# TEMP.net
KiCad netlist of a schematic drawn in EAGLE
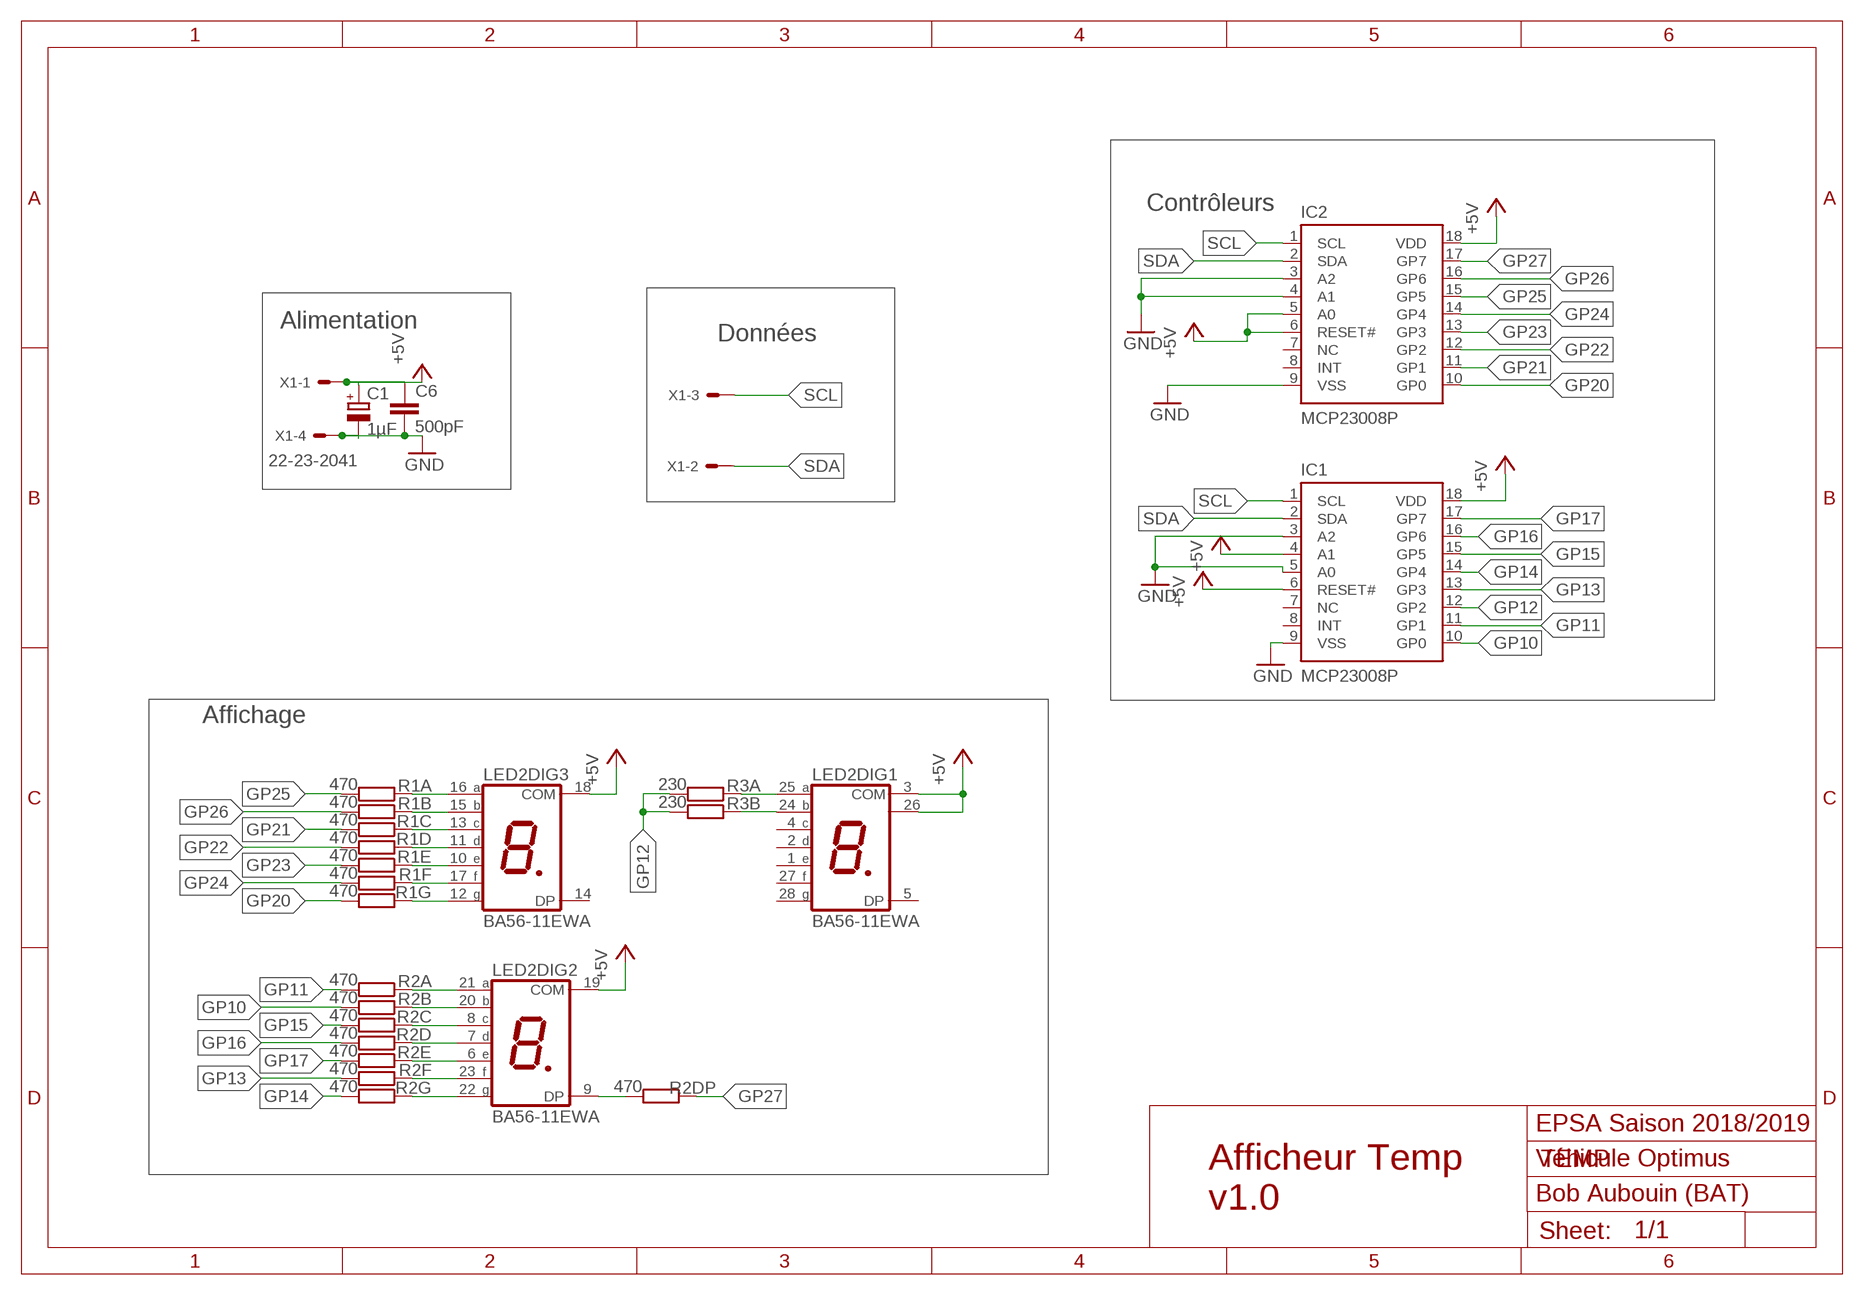
[diagram p0: schematic, sheet 1]

(export (version "E")
  (design (tool "Eeschema 10.0.6"))
  (components
    (comp (ref "C1")
      (value "1µF")
      (footprint "eagle-import:B45181A")
      (libsource (lib "eagle-import") (part "CPOL-EUB45181A"))
    )
    (comp (ref "C6")
      (value "500pF")
      (footprint "eagle-import:C025-025X050")
      (libsource (lib "eagle-import") (part "C-EU025-025X050"))
    )
    (comp (ref "IC1")
      (value "MCP23008P")
      (footprint "eagle-import:DIL18")
      (libsource (lib "eagle-import") (part "MCP23008P"))
    )
    (comp (ref "IC2")
      (value "MCP23008P")
      (footprint "eagle-import:DIL18")
      (libsource (lib "eagle-import") (part "MCP23008P"))
    )
    (comp (ref "LED2")
      (value "BA56-11EWA")
      (footprint "eagle-import:BA_BC56")
      (libsource (lib "eagle-import") (part "B?56-11WAAE"))
    )
    (comp (ref "R1A")
      (value "470")
      (footprint "eagle-import:0204_7")
      (libsource (lib "eagle-import") (part "R-EU_0204/7"))
    )
    (comp (ref "R1B")
      (value "470")
      (footprint "eagle-import:0204_7")
      (libsource (lib "eagle-import") (part "R-EU_0204/7"))
    )
    (comp (ref "R1C")
      (value "470")
      (footprint "eagle-import:0204_7")
      (libsource (lib "eagle-import") (part "R-EU_0204/7"))
    )
    (comp (ref "R1D")
      (value "470")
      (footprint "eagle-import:0204_7")
      (libsource (lib "eagle-import") (part "R-EU_0204/7"))
    )
    (comp (ref "R1E")
      (value "470")
      (footprint "eagle-import:0204_7")
      (libsource (lib "eagle-import") (part "R-EU_0204/7"))
    )
    (comp (ref "R1F")
      (value "470")
      (footprint "eagle-import:0204_7")
      (libsource (lib "eagle-import") (part "R-EU_0204/7"))
    )
    (comp (ref "R1G")
      (value "470")
      (footprint "eagle-import:0204_7")
      (libsource (lib "eagle-import") (part "R-EU_0204/7"))
    )
    (comp (ref "R2A")
      (value "470")
      (footprint "eagle-import:0204_7")
      (libsource (lib "eagle-import") (part "R-EU_0204/7"))
    )
    (comp (ref "R2B")
      (value "470")
      (footprint "eagle-import:0204_7")
      (libsource (lib "eagle-import") (part "R-EU_0204/7"))
    )
    (comp (ref "R2C")
      (value "470")
      (footprint "eagle-import:0204_7")
      (libsource (lib "eagle-import") (part "R-EU_0204/7"))
    )
    (comp (ref "R2D")
      (value "470")
      (footprint "eagle-import:0204_7")
      (libsource (lib "eagle-import") (part "R-EU_0204/7"))
    )
    (comp (ref "R2DP")
      (value "470")
      (footprint "eagle-import:0204_7")
      (libsource (lib "eagle-import") (part "R-EU_0204/7"))
    )
    (comp (ref "R2E")
      (value "470")
      (footprint "eagle-import:0204_7")
      (libsource (lib "eagle-import") (part "R-EU_0204/7"))
    )
    (comp (ref "R2F")
      (value "470")
      (footprint "eagle-import:0204_7")
      (libsource (lib "eagle-import") (part "R-EU_0204/7"))
    )
    (comp (ref "R2G")
      (value "470")
      (footprint "eagle-import:0204_7")
      (libsource (lib "eagle-import") (part "R-EU_0204/7"))
    )
    (comp (ref "R3A")
      (value "230")
      (footprint "eagle-import:0204_7")
      (libsource (lib "eagle-import") (part "R-EU_0204/7"))
    )
    (comp (ref "R3B")
      (value "230")
      (footprint "eagle-import:0204_7")
      (libsource (lib "eagle-import") (part "R-EU_0204/7"))
    )
    (comp (ref "X1")
      (value "22-23-2041")
      (footprint "eagle-import:22-23-2041")
      (fields (field (name "MF") "MOLEX"))
      (libsource (lib "eagle-import") (part "22-23-2041"))
    )
  )
  (nets
    (net (code "1") (name "+5V") (class "Default")
      (node (ref "C1") (pin "+") (pinfunction "+_+") (pintype "passive"))
      (node (ref "C6") (pin "1") (pinfunction "1_1") (pintype "passive"))
      (node (ref "IC1") (pin "18") (pinfunction "VDD_18") (pintype "power_in"))
      (node (ref "IC1") (pin "4") (pinfunction "A1_4") (pintype "input"))
      (node (ref "IC1") (pin "6") (pinfunction "RESET#_6") (pintype "input"))
      (node (ref "IC2") (pin "18") (pinfunction "VDD_18") (pintype "power_in"))
      (node (ref "IC2") (pin "5") (pinfunction "A0_5") (pintype "input"))
      (node (ref "IC2") (pin "6") (pinfunction "RESET#_6") (pintype "input"))
      (node (ref "LED2") (pin "18") (pinfunction "COM_18") (pintype "passive"))
      (node (ref "LED2") (pin "19") (pinfunction "COM_19") (pintype "passive"))
      (node (ref "LED2") (pin "26") (pinfunction "COM_26") (pintype "passive"))
      (node (ref "LED2") (pin "3") (pinfunction "COM_3") (pintype "passive"))
      (node (ref "X1") (pin "1") (pinfunction "S_1") (pintype "passive"))
    )
    (net (code "2") (name "GND") (class "Default")
      (node (ref "C1") (pin "-") (pinfunction "-_-") (pintype "passive"))
      (node (ref "C6") (pin "2") (pinfunction "2_2") (pintype "passive"))
      (node (ref "IC1") (pin "3") (pinfunction "A2_3") (pintype "input"))
      (node (ref "IC1") (pin "5") (pinfunction "A0_5") (pintype "input"))
      (node (ref "IC1") (pin "9") (pinfunction "VSS_9") (pintype "power_in"))
      (node (ref "IC2") (pin "3") (pinfunction "A2_3") (pintype "input"))
      (node (ref "IC2") (pin "4") (pinfunction "A1_4") (pintype "input"))
      (node (ref "IC2") (pin "9") (pinfunction "VSS_9") (pintype "power_in"))
      (node (ref "X1") (pin "4") (pinfunction "S_4") (pintype "passive"))
    )
    (net (code "3") (name "GP10") (class "Default")
      (node (ref "IC1") (pin "10") (pinfunction "GP0_10") (pintype "bidirectional"))
      (node (ref "R2B") (pin "2") (pinfunction "2_2") (pintype "passive"))
    )
    (net (code "4") (name "GP11") (class "Default")
      (node (ref "IC1") (pin "11") (pinfunction "GP1_11") (pintype "bidirectional"))
      (node (ref "R2A") (pin "2") (pinfunction "2_2") (pintype "passive"))
    )
    (net (code "5") (name "GP12") (class "Default")
      (node (ref "IC1") (pin "12") (pinfunction "GP2_12") (pintype "bidirectional"))
      (node (ref "R3A") (pin "2") (pinfunction "2_2") (pintype "passive"))
      (node (ref "R3B") (pin "2") (pinfunction "2_2") (pintype "passive"))
    )
    (net (code "6") (name "GP13") (class "Default")
      (node (ref "IC1") (pin "13") (pinfunction "GP3_13") (pintype "bidirectional"))
      (node (ref "R2F") (pin "2") (pinfunction "2_2") (pintype "passive"))
    )
    (net (code "7") (name "GP14") (class "Default")
      (node (ref "IC1") (pin "14") (pinfunction "GP4_14") (pintype "bidirectional"))
      (node (ref "R2G") (pin "2") (pinfunction "2_2") (pintype "passive"))
    )
    (net (code "8") (name "GP15") (class "Default")
      (node (ref "IC1") (pin "15") (pinfunction "GP5_15") (pintype "bidirectional"))
      (node (ref "R2C") (pin "2") (pinfunction "2_2") (pintype "passive"))
    )
    (net (code "9") (name "GP16") (class "Default")
      (node (ref "IC1") (pin "16") (pinfunction "GP6_16") (pintype "bidirectional"))
      (node (ref "R2D") (pin "2") (pinfunction "2_2") (pintype "passive"))
    )
    (net (code "10") (name "GP17") (class "Default")
      (node (ref "IC1") (pin "17") (pinfunction "GP7_17") (pintype "bidirectional"))
      (node (ref "R2E") (pin "2") (pinfunction "2_2") (pintype "passive"))
    )
    (net (code "11") (name "GP20") (class "Default")
      (node (ref "IC2") (pin "10") (pinfunction "GP0_10") (pintype "bidirectional"))
      (node (ref "R1G") (pin "2") (pinfunction "2_2") (pintype "passive"))
    )
    (net (code "12") (name "GP21") (class "Default")
      (node (ref "IC2") (pin "11") (pinfunction "GP1_11") (pintype "bidirectional"))
      (node (ref "R1C") (pin "2") (pinfunction "2_2") (pintype "passive"))
    )
    (net (code "13") (name "GP22") (class "Default")
      (node (ref "IC2") (pin "12") (pinfunction "GP2_12") (pintype "bidirectional"))
      (node (ref "R1D") (pin "2") (pinfunction "2_2") (pintype "passive"))
    )
    (net (code "14") (name "GP23") (class "Default")
      (node (ref "IC2") (pin "13") (pinfunction "GP3_13") (pintype "bidirectional"))
      (node (ref "R1E") (pin "2") (pinfunction "2_2") (pintype "passive"))
    )
    (net (code "15") (name "GP24") (class "Default")
      (node (ref "IC2") (pin "14") (pinfunction "GP4_14") (pintype "bidirectional"))
      (node (ref "R1F") (pin "2") (pinfunction "2_2") (pintype "passive"))
    )
    (net (code "16") (name "GP25") (class "Default")
      (node (ref "IC2") (pin "15") (pinfunction "GP5_15") (pintype "bidirectional"))
      (node (ref "R1A") (pin "2") (pinfunction "2_2") (pintype "passive"))
    )
    (net (code "17") (name "GP26") (class "Default")
      (node (ref "IC2") (pin "16") (pinfunction "GP6_16") (pintype "bidirectional"))
      (node (ref "R1B") (pin "2") (pinfunction "2_2") (pintype "passive"))
    )
    (net (code "18") (name "GP27") (class "Default")
      (node (ref "IC2") (pin "17") (pinfunction "GP7_17") (pintype "bidirectional"))
      (node (ref "R2DP") (pin "1") (pinfunction "1_1") (pintype "passive"))
    )
    (net (code "19") (name "Net-(LED2A-A)") (class "Default")
      (node (ref "LED2") (pin "25") (pinfunction "A_25") (pintype "passive"))
      (node (ref "R3A") (pin "1") (pinfunction "1_1") (pintype "passive"))
    )
    (net (code "20") (name "Net-(LED2A-B)") (class "Default")
      (node (ref "LED2") (pin "24") (pinfunction "B_24") (pintype "passive"))
      (node (ref "R3B") (pin "1") (pinfunction "1_1") (pintype "passive"))
    )
    (net (code "21") (name "Net-(LED2B-A)") (class "Default")
      (node (ref "LED2") (pin "21") (pinfunction "A_21") (pintype "passive"))
      (node (ref "R2A") (pin "1") (pinfunction "1_1") (pintype "passive"))
    )
    (net (code "22") (name "Net-(LED2B-B)") (class "Default")
      (node (ref "LED2") (pin "20") (pinfunction "B_20") (pintype "passive"))
      (node (ref "R2B") (pin "1") (pinfunction "1_1") (pintype "passive"))
    )
    (net (code "23") (name "Net-(LED2B-C)") (class "Default")
      (node (ref "LED2") (pin "8") (pinfunction "C_8") (pintype "passive"))
      (node (ref "R2C") (pin "1") (pinfunction "1_1") (pintype "passive"))
    )
    (net (code "24") (name "Net-(LED2B-D)") (class "Default")
      (node (ref "LED2") (pin "7") (pinfunction "D_7") (pintype "passive"))
      (node (ref "R2D") (pin "1") (pinfunction "1_1") (pintype "passive"))
    )
    (net (code "25") (name "Net-(LED2B-DP)") (class "Default")
      (node (ref "LED2") (pin "9") (pinfunction "DP_9") (pintype "passive"))
      (node (ref "R2DP") (pin "2") (pinfunction "2_2") (pintype "passive"))
    )
    (net (code "26") (name "Net-(LED2B-E)") (class "Default")
      (node (ref "LED2") (pin "6") (pinfunction "E_6") (pintype "passive"))
      (node (ref "R2E") (pin "1") (pinfunction "1_1") (pintype "passive"))
    )
    (net (code "27") (name "Net-(LED2B-F)") (class "Default")
      (node (ref "LED2") (pin "23") (pinfunction "F_23") (pintype "passive"))
      (node (ref "R2F") (pin "1") (pinfunction "1_1") (pintype "passive"))
    )
    (net (code "28") (name "Net-(LED2B-G)") (class "Default")
      (node (ref "LED2") (pin "22") (pinfunction "G_22") (pintype "passive"))
      (node (ref "R2G") (pin "1") (pinfunction "1_1") (pintype "passive"))
    )
    (net (code "29") (name "Net-(LED2C-A)") (class "Default")
      (node (ref "LED2") (pin "16") (pinfunction "A_16") (pintype "passive"))
      (node (ref "R1A") (pin "1") (pinfunction "1_1") (pintype "passive"))
    )
    (net (code "30") (name "Net-(LED2C-B)") (class "Default")
      (node (ref "LED2") (pin "15") (pinfunction "B_15") (pintype "passive"))
      (node (ref "R1B") (pin "1") (pinfunction "1_1") (pintype "passive"))
    )
    (net (code "31") (name "Net-(LED2C-C)") (class "Default")
      (node (ref "LED2") (pin "13") (pinfunction "C_13") (pintype "passive"))
      (node (ref "R1C") (pin "1") (pinfunction "1_1") (pintype "passive"))
    )
    (net (code "32") (name "Net-(LED2C-D)") (class "Default")
      (node (ref "LED2") (pin "11") (pinfunction "D_11") (pintype "passive"))
      (node (ref "R1D") (pin "1") (pinfunction "1_1") (pintype "passive"))
    )
    (net (code "33") (name "Net-(LED2C-E)") (class "Default")
      (node (ref "LED2") (pin "10") (pinfunction "E_10") (pintype "passive"))
      (node (ref "R1E") (pin "1") (pinfunction "1_1") (pintype "passive"))
    )
    (net (code "34") (name "Net-(LED2C-F)") (class "Default")
      (node (ref "LED2") (pin "17") (pinfunction "F_17") (pintype "passive"))
      (node (ref "R1F") (pin "1") (pinfunction "1_1") (pintype "passive"))
    )
    (net (code "35") (name "Net-(LED2C-G)") (class "Default")
      (node (ref "LED2") (pin "12") (pinfunction "G_12") (pintype "passive"))
      (node (ref "R1G") (pin "1") (pinfunction "1_1") (pintype "passive"))
    )
    (net (code "36") (name "SCL") (class "Default")
      (node (ref "IC1") (pin "1") (pinfunction "SCL_1") (pintype "input"))
      (node (ref "IC2") (pin "1") (pinfunction "SCL_1") (pintype "input"))
      (node (ref "X1") (pin "3") (pinfunction "S_3") (pintype "passive"))
    )
    (net (code "37") (name "SDA") (class "Default")
      (node (ref "IC1") (pin "2") (pinfunction "SDA_2") (pintype "bidirectional"))
      (node (ref "IC2") (pin "2") (pinfunction "SDA_2") (pintype "bidirectional"))
      (node (ref "X1") (pin "2") (pinfunction "S_2") (pintype "passive"))
    )
    (net (code "38") (name "unconnected-(IC1-INT-Pad8)") (class "Default")
      (node (ref "IC1") (pin "8") (pinfunction "INT_8") (pintype "output"))
    )
    (net (code "39") (name "unconnected-(IC1-NC-Pad7)") (class "Default")
      (node (ref "IC1") (pin "7") (pinfunction "NC_7") (pintype "no_connect"))
    )
    (net (code "40") (name "unconnected-(IC2-INT-Pad8)") (class "Default")
      (node (ref "IC2") (pin "8") (pinfunction "INT_8") (pintype "output"))
    )
    (net (code "41") (name "unconnected-(IC2-NC-Pad7)") (class "Default")
      (node (ref "IC2") (pin "7") (pinfunction "NC_7") (pintype "no_connect"))
    )
    (net (code "42") (name "unconnected-(LED2A-C-Pad4)") (class "Default")
      (node (ref "LED2") (pin "4") (pinfunction "C_4") (pintype "passive"))
    )
    (net (code "43") (name "unconnected-(LED2A-D-Pad2)") (class "Default")
      (node (ref "LED2") (pin "2") (pinfunction "D_2") (pintype "passive"))
    )
    (net (code "44") (name "unconnected-(LED2A-DP-Pad5)") (class "Default")
      (node (ref "LED2") (pin "5") (pinfunction "DP_5") (pintype "passive"))
    )
    (net (code "45") (name "unconnected-(LED2A-E-Pad1)") (class "Default")
      (node (ref "LED2") (pin "1") (pinfunction "E_1") (pintype "passive"))
    )
    (net (code "46") (name "unconnected-(LED2A-F-Pad27)") (class "Default")
      (node (ref "LED2") (pin "27") (pinfunction "F_27") (pintype "passive"))
    )
    (net (code "47") (name "unconnected-(LED2A-G-Pad28)") (class "Default")
      (node (ref "LED2") (pin "28") (pinfunction "G_28") (pintype "passive"))
    )
    (net (code "48") (name "unconnected-(LED2C-DP-Pad14)") (class "Default")
      (node (ref "LED2") (pin "14") (pinfunction "DP_14") (pintype "passive"))
    )
  )
)
